# MasterCtrl.net
KiCad netlist of a schematic drawn in EasyEDA Pro
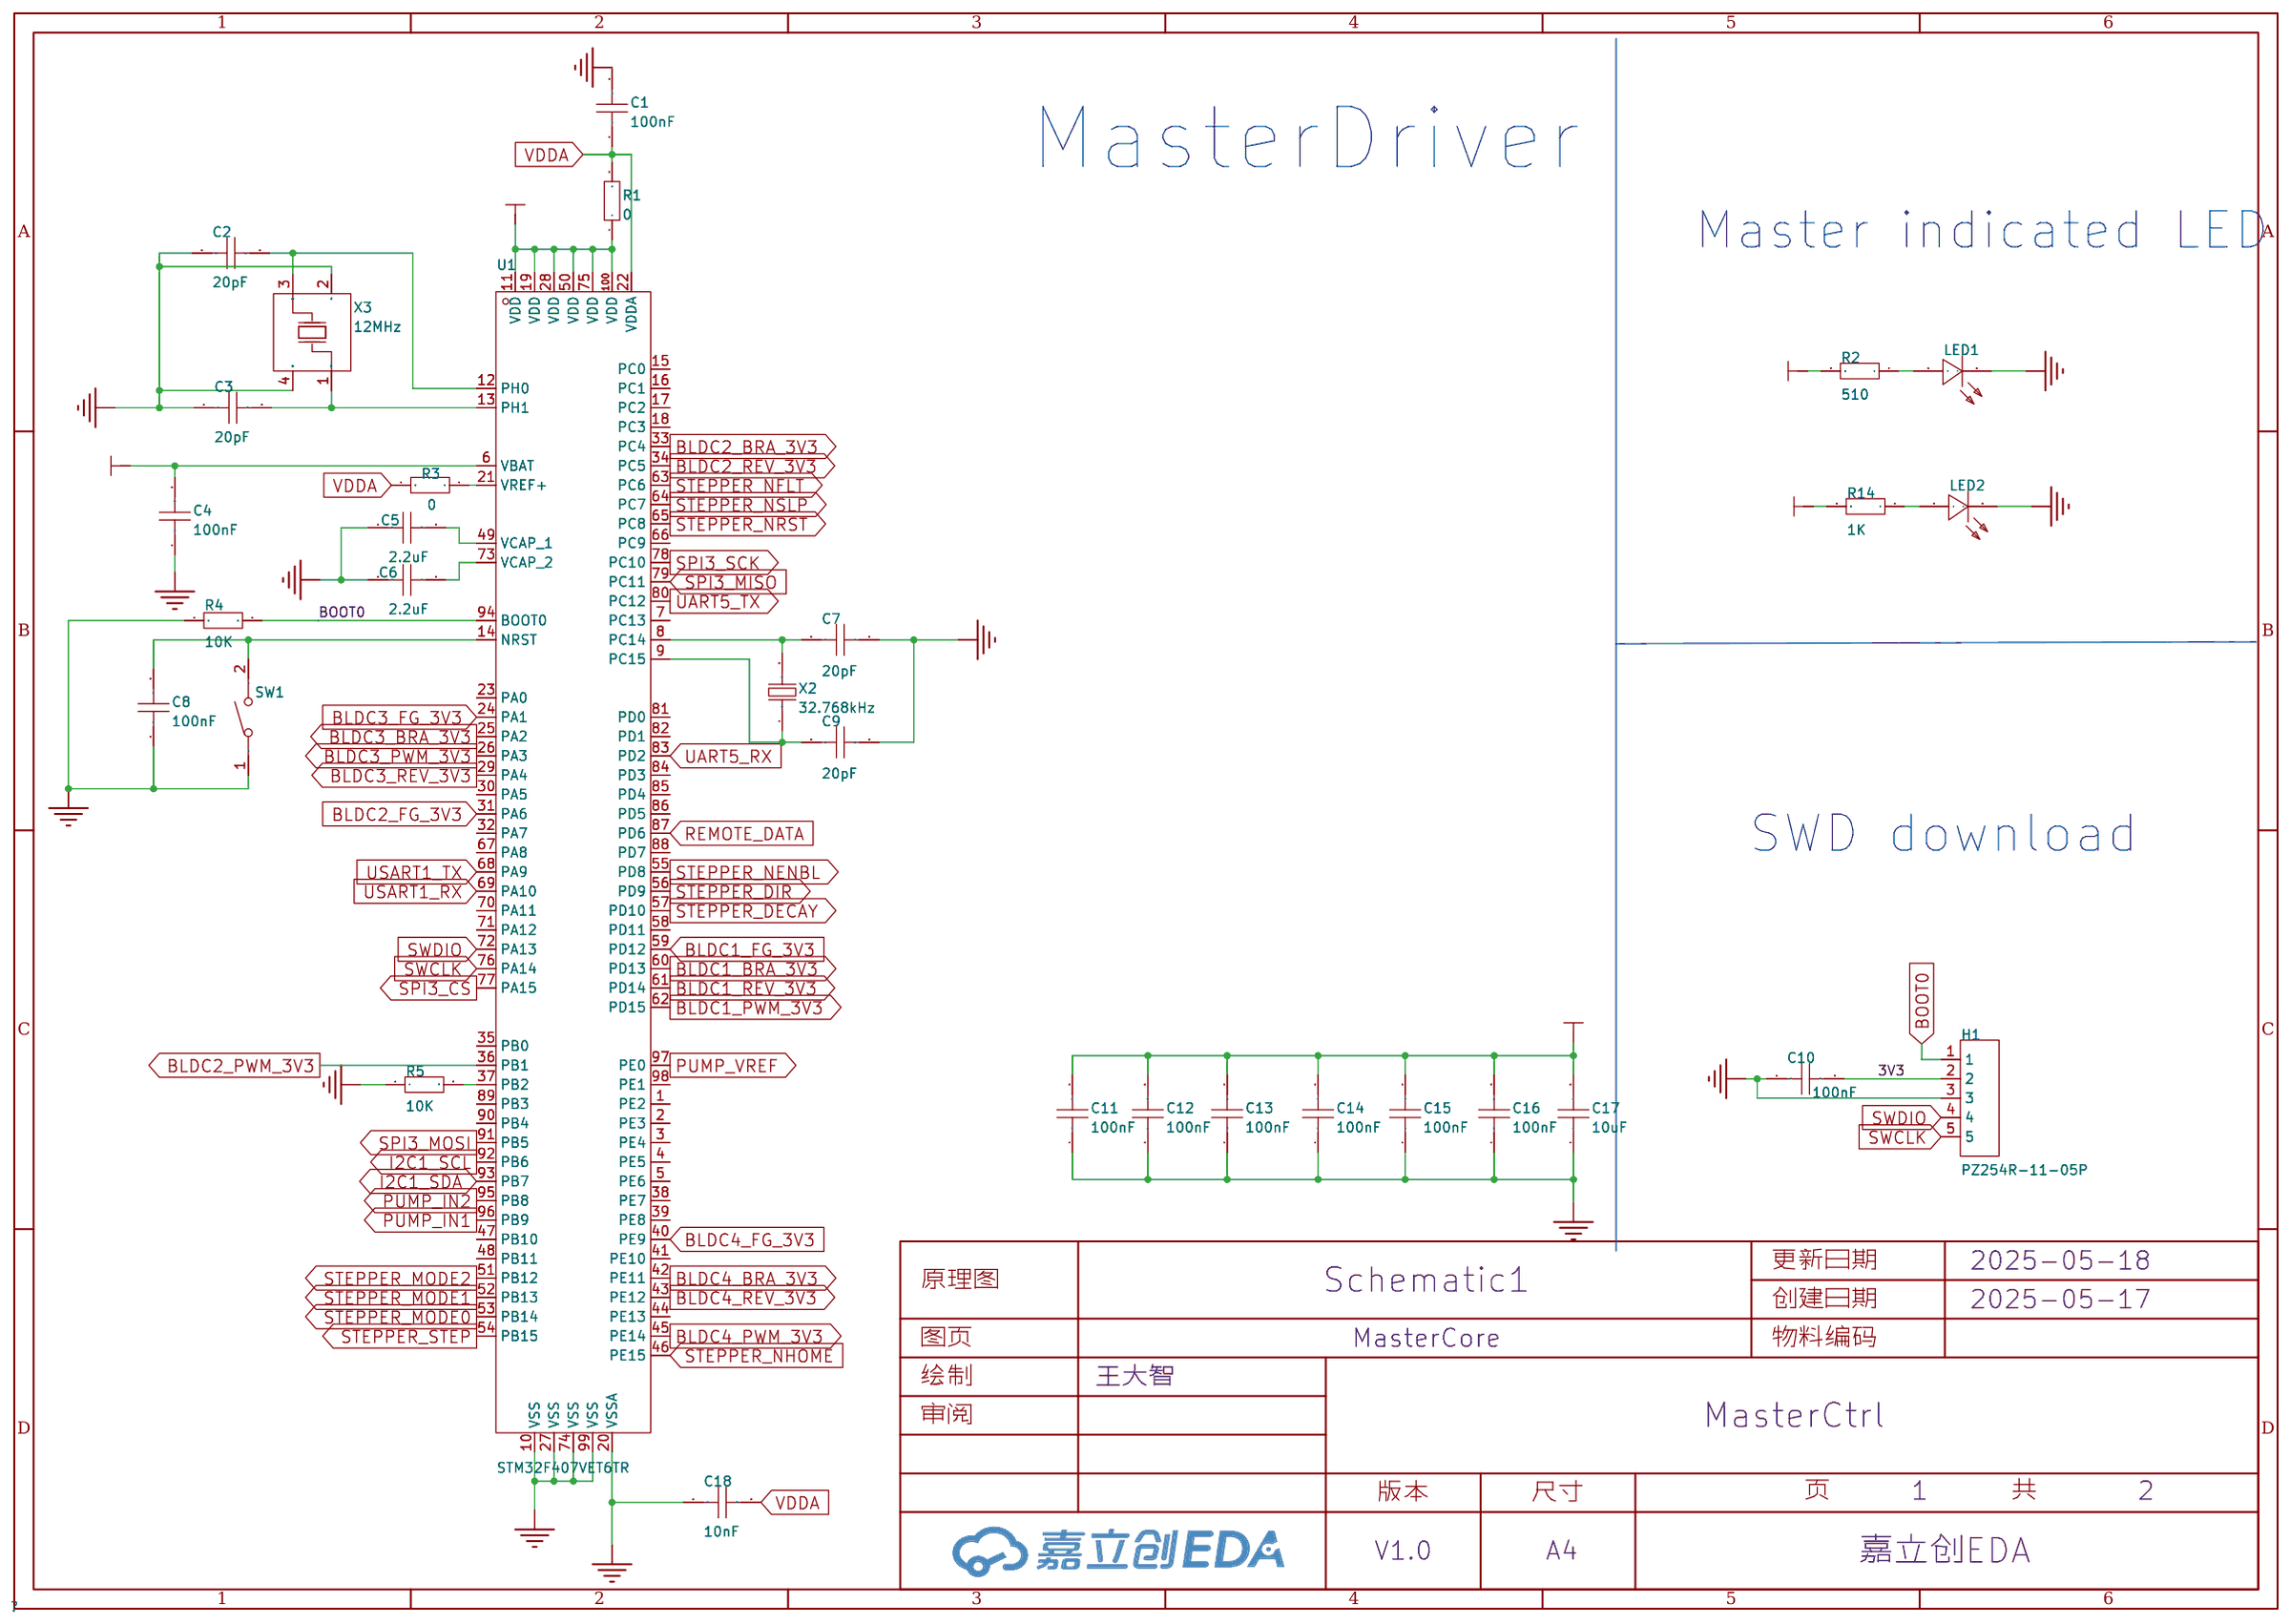
[diagram p0: MasterCore]
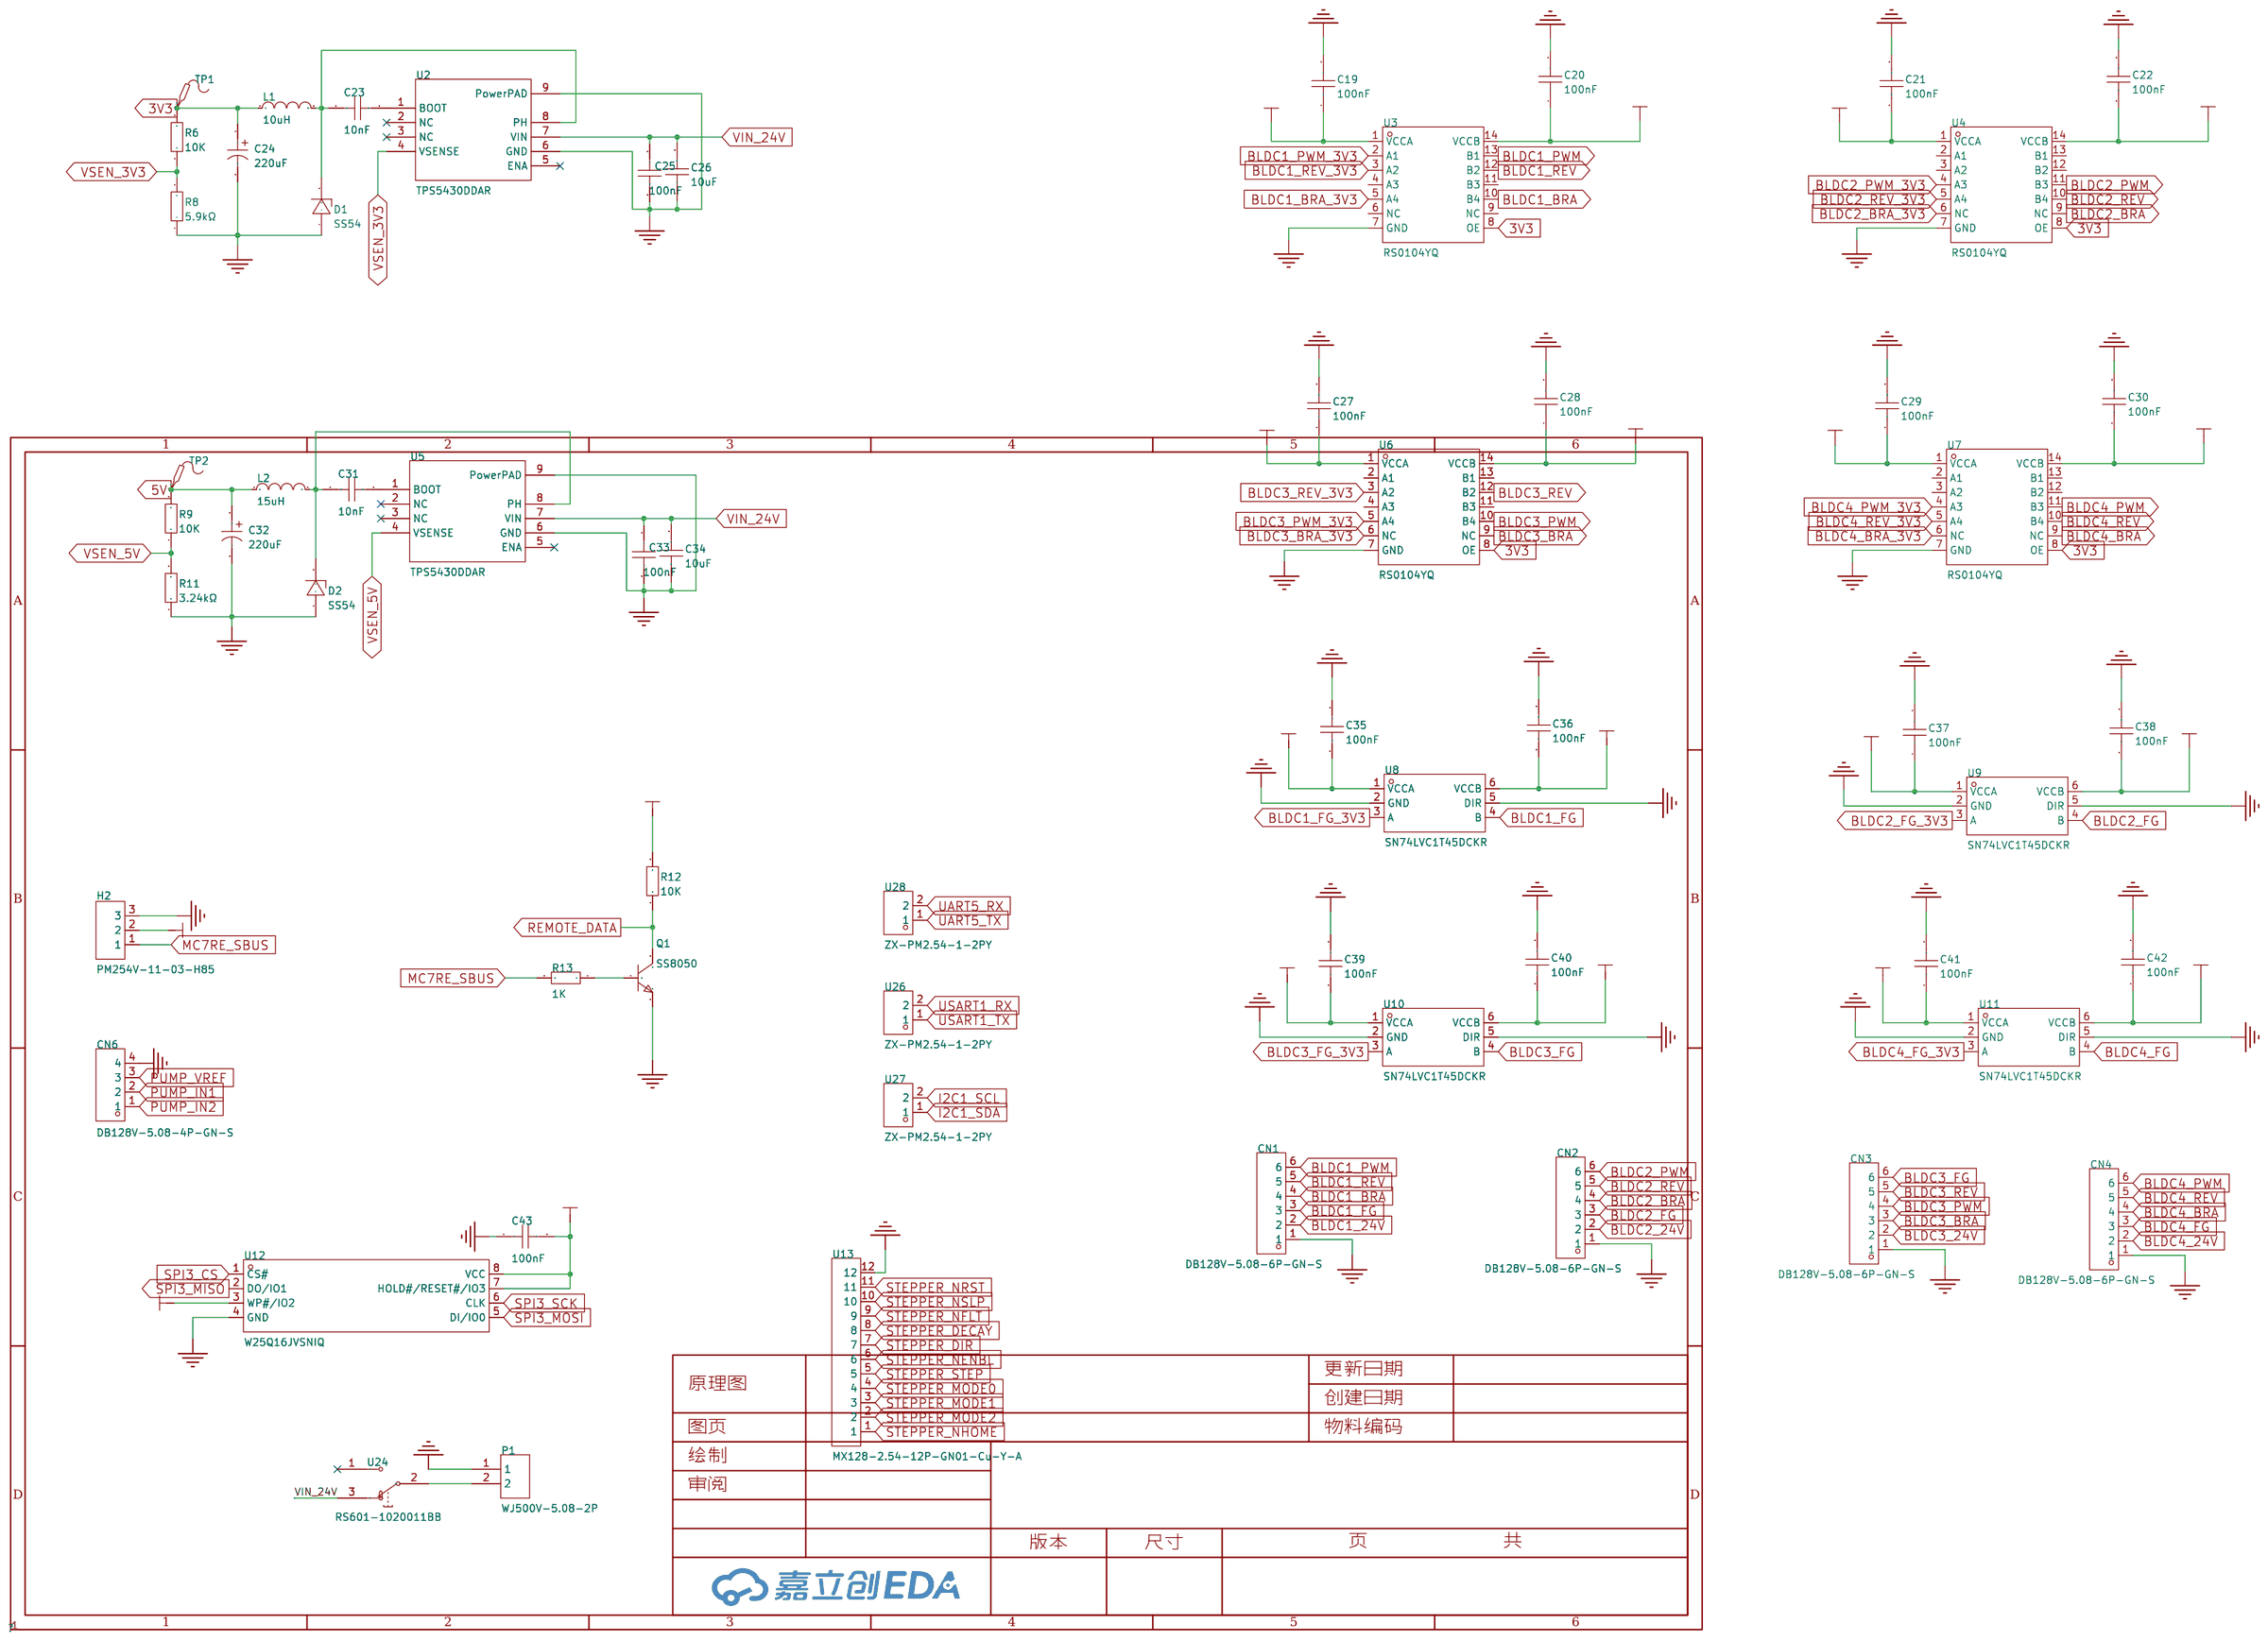
[diagram p1: ExternalCircuit]

(export (version "E")
  (design (tool "Eeschema 10.0.6"))
  (components
    (comp (ref "C1")
      (value "100nF")
      (footprint "easyedapro:C0603")
      (libsource (lib "easyedapro") (part "CapAcitance"))
    )
    (comp (ref "C2")
      (value "20pF")
      (footprint "easyedapro:C0603")
      (libsource (lib "easyedapro") (part "CapAcitance"))
    )
    (comp (ref "C3")
      (value "20pF")
      (footprint "easyedapro:C0603")
      (libsource (lib "easyedapro") (part "CapAcitance"))
    )
    (comp (ref "C4")
      (value "100nF")
      (footprint "easyedapro:C0603")
      (libsource (lib "easyedapro") (part "CapAcitance"))
    )
    (comp (ref "C5")
      (value "2.2uF")
      (footprint "easyedapro:C0603")
      (libsource (lib "easyedapro") (part "CapAcitance"))
    )
    (comp (ref "C6")
      (value "2.2uF")
      (footprint "easyedapro:C0603")
      (libsource (lib "easyedapro") (part "CapAcitance"))
    )
    (comp (ref "C7")
      (value "20pF")
      (footprint "easyedapro:C0603")
      (libsource (lib "easyedapro") (part "CapAcitance"))
    )
    (comp (ref "C8")
      (value "100nF")
      (footprint "easyedapro:C0603")
      (libsource (lib "easyedapro") (part "CapAcitance"))
    )
    (comp (ref "C9")
      (value "20pF")
      (footprint "easyedapro:C0603")
      (libsource (lib "easyedapro") (part "CapAcitance"))
    )
    (comp (ref "C10")
      (value "100nF")
      (footprint "easyedapro:C0603")
      (libsource (lib "easyedapro") (part "CapAcitance"))
    )
    (comp (ref "C11")
      (value "100nF")
      (footprint "easyedapro:C0603")
      (libsource (lib "easyedapro") (part "CapAcitance"))
    )
    (comp (ref "C12")
      (value "100nF")
      (footprint "easyedapro:C0603")
      (libsource (lib "easyedapro") (part "CapAcitance"))
    )
    (comp (ref "C13")
      (value "100nF")
      (footprint "easyedapro:C0603")
      (libsource (lib "easyedapro") (part "CapAcitance"))
    )
    (comp (ref "C14")
      (value "100nF")
      (footprint "easyedapro:C0603")
      (libsource (lib "easyedapro") (part "CapAcitance"))
    )
    (comp (ref "C15")
      (value "100nF")
      (footprint "easyedapro:C0603")
      (libsource (lib "easyedapro") (part "CapAcitance"))
    )
    (comp (ref "C16")
      (value "100nF")
      (footprint "easyedapro:C0603")
      (libsource (lib "easyedapro") (part "CapAcitance"))
    )
    (comp (ref "C17")
      (value "10uF")
      (footprint "easyedapro:C0603")
      (libsource (lib "easyedapro") (part "CapAcitance"))
    )
    (comp (ref "C18")
      (value "10nF")
      (footprint "easyedapro:C0603")
      (libsource (lib "easyedapro") (part "CapAcitance"))
    )
    (comp (ref "H1")
      (value "PZ254R-11-05P")
      (footprint "easyedapro:HDR-TH_5P-P2.54-H-M-W10.4")
      (fields (field (name "Manufacturer") "XFCN(兴飞)"))
      (libsource (lib "easyedapro") (part "PZ254R-11-05P"))
    )
    (comp (ref "LED1")
      (value "SZYY0805R")
      (footprint "easyedapro:LED0805-R-RD")
      (fields (field (name "Manufacturer") "yongyu(永裕光电)"))
      (libsource (lib "easyedapro") (part "SZYY0805R"))
    )
    (comp (ref "LED2")
      (value "SZYY0805R")
      (footprint "easyedapro:LED0805-R-RD")
      (fields (field (name "Manufacturer") "yongyu(永裕光电)"))
      (libsource (lib "easyedapro") (part "SZYY0805R"))
    )
    (comp (ref "R1") (value "0") (footprint "easyedapro:R0603") (libsource (lib "easyedapro") (part "电阻")))
    (comp (ref "R2") (value "510") (footprint "easyedapro:R0603") (libsource (lib "easyedapro") (part "电阻")))
    (comp (ref "R3") (value "0") (footprint "easyedapro:R0603") (libsource (lib "easyedapro") (part "电阻")))
    (comp (ref "R4") (value "10K") (footprint "easyedapro:R0603") (libsource (lib "easyedapro") (part "电阻")))
    (comp (ref "R5") (value "10K") (footprint "easyedapro:R0603") (libsource (lib "easyedapro") (part "电阻")))
    (comp (ref "R14") (value "1K") (footprint "easyedapro:R0603") (libsource (lib "easyedapro") (part "电阻")))
    (comp (ref "SW1")
      (value "TS-1088-AR02016")
      (footprint "easyedapro:SW-SMD_L3.9-W3.0-P4.45")
      (fields (field (name "Manufacturer") "XUNPU(讯普)"))
      (libsource (lib "easyedapro") (part "TS-1088-AR02016"))
    )
    (comp (ref "U1")
      (value "STM32F407VET6TR")
      (footprint "easyedapro:LQFP-100_L14.0-W14.0-P0.50-LS16.0-BL")
      (description "CPU内核:ARM-M4;CPU最大主频:168MHz;应用领域:-;")
      (fields (field (name "Manufacturer") "ST(意法半导体)"))
      (libsource (lib "easyedapro") (part "STM32F407VET6TR"))
    )
    (comp (ref "X2")
      (value "32.768kHz")
      (footprint "easyedapro:FC-135R_L3.2-W1.5")
      (description "晶振类型:贴片晶振;频率:32.768kHz;常温频差:±20ppm;负载电容:12.5pF;")
      (fields (field (name "Manufacturer Part") "Q13FC13500004") (field (name "Manufacturer") "EPSON(爱普生)"))
      (libsource (lib "easyedapro") (part "Q13FC1350000400"))
    )
    (comp (ref "X3")
      (value "12MHz")
      (footprint "easyedapro:CRYSTAL-SMD_4P-L3.2-W2.5-BL")
      (description "晶振类型:贴片晶振;频率:12MHz;常温频差:±10ppm;负载电容:20pF;频率稳定度:±20ppm;")
      (fields (field (name "Manufacturer Part") "X322512MSB4SI") (field (name "Manufacturer") "YXC(扬兴晶振)"))
      (libsource (lib "easyedapro") (part "X322512MSB4SI"))
    )
    (comp (ref "C19")
      (value "100nF")
      (footprint "easyedapro:C0603")
      (libsource (lib "easyedapro") (part "CapAcitance"))
    )
    (comp (ref "C20")
      (value "100nF")
      (footprint "easyedapro:C0603")
      (libsource (lib "easyedapro") (part "CapAcitance"))
    )
    (comp (ref "C21")
      (value "100nF")
      (footprint "easyedapro:C0603")
      (libsource (lib "easyedapro") (part "CapAcitance"))
    )
    (comp (ref "C22")
      (value "100nF")
      (footprint "easyedapro:C0603")
      (libsource (lib "easyedapro") (part "CapAcitance"))
    )
    (comp (ref "C23")
      (value "10nF")
      (footprint "easyedapro:C0603")
      (libsource (lib "easyedapro") (part "CapAcitance"))
    )
    (comp (ref "C24")
      (value "220uF")
      (footprint "easyedapro:CAP-SMD_BD8.0-L8.3-W8.3-FD")
      (description "容值:220uF;精度:±20%;额定电压:35V;纹波电流:175mA@120Hz;")
      (fields
        (field (name "Manufacturer Part") "GVT1V227M0810CNVC")
        (field (name "Manufacturer") "HRK(鸿瑞凯电子)")
      )
      (libsource (lib "easyedapro") (part "GVT1V227M0810CNVC"))
    )
    (comp (ref "C25")
      (value "100nF")
      (footprint "easyedapro:C0603")
      (libsource (lib "easyedapro") (part "CapAcitance"))
    )
    (comp (ref "C26")
      (value "10uF")
      (footprint "easyedapro:C1206")
      (description "容值:10uF;精度:±10%;额定电压:50V;温度系数:X5R;")
      (fields
        (field (name "Manufacturer Part") "HGC1206R5106K500NSPJ")
        (field (name "Manufacturer") "Chinocera(华瓷)")
      )
      (libsource (lib "easyedapro") (part "HGC1206R5106K500NSPJ"))
    )
    (comp (ref "C27")
      (value "100nF")
      (footprint "easyedapro:C0603")
      (libsource (lib "easyedapro") (part "CapAcitance"))
    )
    (comp (ref "C28")
      (value "100nF")
      (footprint "easyedapro:C0603")
      (libsource (lib "easyedapro") (part "CapAcitance"))
    )
    (comp (ref "C29")
      (value "100nF")
      (footprint "easyedapro:C0603")
      (libsource (lib "easyedapro") (part "CapAcitance"))
    )
    (comp (ref "C30")
      (value "100nF")
      (footprint "easyedapro:C0603")
      (libsource (lib "easyedapro") (part "CapAcitance"))
    )
    (comp (ref "C31")
      (value "10nF")
      (footprint "easyedapro:C0603")
      (libsource (lib "easyedapro") (part "CapAcitance"))
    )
    (comp (ref "C32")
      (value "220uF")
      (footprint "easyedapro:CAP-SMD_BD8.0-L8.3-W8.3-FD")
      (description "容值:220uF;精度:±20%;额定电压:35V;纹波电流:175mA@120Hz;")
      (fields
        (field (name "Manufacturer Part") "GVT1V227M0810CNVC")
        (field (name "Manufacturer") "HRK(鸿瑞凯电子)")
      )
      (libsource (lib "easyedapro") (part "GVT1V227M0810CNVC"))
    )
    (comp (ref "C33")
      (value "100nF")
      (footprint "easyedapro:C0603")
      (libsource (lib "easyedapro") (part "CapAcitance"))
    )
    (comp (ref "C34")
      (value "10uF")
      (footprint "easyedapro:C1206")
      (description "容值:10uF;精度:±10%;额定电压:50V;温度系数:X5R;")
      (fields
        (field (name "Manufacturer Part") "HGC1206R5106K500NSPJ")
        (field (name "Manufacturer") "Chinocera(华瓷)")
      )
      (libsource (lib "easyedapro") (part "HGC1206R5106K500NSPJ"))
    )
    (comp (ref "C35")
      (value "100nF")
      (footprint "easyedapro:C0603")
      (libsource (lib "easyedapro") (part "CapAcitance"))
    )
    (comp (ref "C36")
      (value "100nF")
      (footprint "easyedapro:C0603")
      (libsource (lib "easyedapro") (part "CapAcitance"))
    )
    (comp (ref "C37")
      (value "100nF")
      (footprint "easyedapro:C0603")
      (libsource (lib "easyedapro") (part "CapAcitance"))
    )
    (comp (ref "C38")
      (value "100nF")
      (footprint "easyedapro:C0603")
      (libsource (lib "easyedapro") (part "CapAcitance"))
    )
    (comp (ref "C39")
      (value "100nF")
      (footprint "easyedapro:C0603")
      (libsource (lib "easyedapro") (part "CapAcitance"))
    )
    (comp (ref "C40")
      (value "100nF")
      (footprint "easyedapro:C0603")
      (libsource (lib "easyedapro") (part "CapAcitance"))
    )
    (comp (ref "C41")
      (value "100nF")
      (footprint "easyedapro:C0603")
      (libsource (lib "easyedapro") (part "CapAcitance"))
    )
    (comp (ref "C42")
      (value "100nF")
      (footprint "easyedapro:C0603")
      (libsource (lib "easyedapro") (part "CapAcitance"))
    )
    (comp (ref "C43")
      (value "100nF")
      (footprint "easyedapro:C0603")
      (libsource (lib "easyedapro") (part "CapAcitance"))
    )
    (comp (ref "CN1")
      (value "DB128V-5.08-6P-GN-S")
      (footprint "easyedapro:CONN-TH_6P-P5.08_DIBO_DB128V-5.08")
      (fields (field (name "Manufacturer") "DORABO(地博电气)"))
      (libsource (lib "easyedapro") (part "DB128V-5.08-6P-GN-S"))
    )
    (comp (ref "CN2")
      (value "DB128V-5.08-6P-GN-S")
      (footprint "easyedapro:CONN-TH_6P-P5.08_DIBO_DB128V-5.08")
      (fields (field (name "Manufacturer") "DORABO(地博电气)"))
      (libsource (lib "easyedapro") (part "DB128V-5.08-6P-GN-S"))
    )
    (comp (ref "CN3")
      (value "DB128V-5.08-6P-GN-S")
      (footprint "easyedapro:CONN-TH_6P-P5.08_DIBO_DB128V-5.08")
      (fields (field (name "Manufacturer") "DORABO(地博电气)"))
      (libsource (lib "easyedapro") (part "DB128V-5.08-6P-GN-S"))
    )
    (comp (ref "CN4")
      (value "DB128V-5.08-6P-GN-S")
      (footprint "easyedapro:CONN-TH_6P-P5.08_DIBO_DB128V-5.08")
      (fields (field (name "Manufacturer") "DORABO(地博电气)"))
      (libsource (lib "easyedapro") (part "DB128V-5.08-6P-GN-S"))
    )
    (comp (ref "CN6")
      (value "DB128V-5.08-4P-GN-S")
      (footprint "easyedapro:CONN-TH_4P-P5.08_DIBO_DB128V-5.08")
      (fields (field (name "Manufacturer") "DORABO(地博电气)"))
      (libsource (lib "easyedapro") (part "DB128V-5.08-4P-GN-S"))
    )
    (comp (ref "D1")
      (value "SS54")
      (footprint "easyedapro:SMA_L4.3-W2.6-LS5.0-FD")
      (description "二极管配置:独立式;正向压降(Vf):550mV@5.0A;直流反向耐压(Vr):40V;整流电流:5A;")
      (fields (field (name "Manufacturer") "宏迦橙"))
      (libsource (lib "easyedapro") (part "SS54_C7420369"))
    )
    (comp (ref "D2")
      (value "SS54")
      (footprint "easyedapro:SMA_L4.3-W2.6-LS5.0-FD")
      (description "二极管配置:独立式;正向压降(Vf):550mV@5.0A;直流反向耐压(Vr):40V;整流电流:5A;")
      (fields (field (name "Manufacturer") "宏迦橙"))
      (libsource (lib "easyedapro") (part "SS54_C7420369"))
    )
    (comp (ref "H2")
      (value "PM254V-11-03-H85")
      (footprint "easyedapro:HDR-TH_3P-P2.54-V-F")
      (description "插孔结构:1x3P;间距:2.54mm;行距:-;安装类型:直插;排数:单排;总孔位数:3P;塑高:-;触头材质:黄铜;触头镀层:-;")
      (fields (field (name "Manufacturer") "XFCN(兴飞)"))
      (libsource (lib "easyedapro") (part "PM254V-11-03-H85"))
    )
    (comp (ref "L1")
      (value "10uH")
      (footprint "easyedapro:IND-SMD_L7.3-W6.8")
      (description "电感值:10uH;精度:±20%;额定电流:4.5A;饱和电流(Isat):5.5A;类型:一体成型电感;")
      (fields (field (name "Manufacturer Part") "FXL0630-100-M") (field (name "Manufacturer") "cjiang(长江微电)"))
      (libsource (lib "easyedapro") (part "FXL0630-100-M"))
    )
    (comp (ref "L2")
      (value "15uH")
      (footprint "easyedapro:IND-SMD_L7.0-W6.6_FXL0630")
      (description "电感值:15uH;精度:±20%;额定电流:3A;饱和电流(Isat):4.5A;类型:一体成型电感;")
      (fields (field (name "Manufacturer Part") "FXL0630-150-M") (field (name "Manufacturer") "cjiang(长江微电)"))
      (libsource (lib "easyedapro") (part "FXL0630-150-M"))
    )
    (comp (ref "P1")
      (value "WJ500V-5.08-2P")
      (footprint "easyedapro:CONN-TH_2P-P5.00_WJ500V-5.08-2P")
      (fields (field (name "Manufacturer") "KANGNEX(康奈克斯电气)"))
      (libsource (lib "easyedapro") (part "WJ500V-5.08-2P-14-00A"))
    )
    (comp (ref "Q1")
      (value "SS8050")
      (footprint "easyedapro:SOT-23-3_L2.9-W1.3-P1.90-LS2.4-BR")
      (description "晶体管类型:NPN;集电极电流(Ic):1.5A;集射极击穿电压(Vceo):25V;耗散功率(Pd):300mW;直流电流增益(hFE):120@100mA,1.0V;")
      (fields (field (name "Manufacturer") "宏嘉诚"))
      (libsource (lib "easyedapro") (part "SS8050_C7420370"))
    )
    (comp (ref "R6") (value "10K") (footprint "easyedapro:R0603") (libsource (lib "easyedapro") (part "电阻")))
    (comp (ref "R8")
      (value "5.9kΩ")
      (footprint "easyedapro:R0603")
      (description "电阻类型:厚膜电阻;阻值:5.9kΩ;精度:±1%;功率:100mW;最大工作电压:75V;温度系数:±100ppm/°C;")
      (fields
        (field (name "Manufacturer Part") "0603WAF5901T5E")
        (field (name "Manufacturer") "UNI-ROYAL(厚声)")
      )
      (libsource (lib "easyedapro") (part "0603WAF5901T5E"))
    )
    (comp (ref "R9") (value "10K") (footprint "easyedapro:R0603") (libsource (lib "easyedapro") (part "电阻")))
    (comp (ref "R11")
      (value "3.24kΩ")
      (footprint "easyedapro:R0603")
      (description "电阻类型:厚膜电阻;阻值:3.24kΩ;精度:±1%;功率:100mW;最大工作电压:75V;温度系数:±100ppm/°C;")
      (fields
        (field (name "Manufacturer Part") "0603WAF3241T5E")
        (field (name "Manufacturer") "UNI-ROYAL(厚声)")
      )
      (libsource (lib "easyedapro") (part "0603WAF3241T5E"))
    )
    (comp (ref "R12") (value "10K") (footprint "easyedapro:R0603") (libsource (lib "easyedapro") (part "电阻")))
    (comp (ref "R13") (value "1K") (footprint "easyedapro:R0603") (libsource (lib "easyedapro") (part "电阻")))
    (comp (ref "TP1")
      (value "~")
      (footprint "easyedapro:Test-Point-0.5mm")
      (description "Test Point 测试点")
      (libsource (lib "easyedapro") (part "Test-Point"))
    )
    (comp (ref "TP2")
      (value "~")
      (footprint "easyedapro:Test-Point-0.5mm")
      (description "Test Point 测试点")
      (libsource (lib "easyedapro") (part "Test-Point"))
    )
    (comp (ref "U2")
      (value "TPS5430DDAR")
      (footprint "easyedapro:ESOP-8_L4.9-W3.9-P1.27-LS6.0-TL-EP")
      (description "功能类型:降压型;输出类型:可调;工作电压:5.5V~36V;输出电压:1.221V~32.04V;输出电流:3A;")
      (fields (field (name "Manufacturer") "TI(德州仪器)"))
      (libsource (lib "easyedapro") (part "TPS5430DDAR"))
    )
    (comp (ref "U3")
      (value "RS0104YQ")
      (footprint "easyedapro:TSSOP-14_L5.0-W4.4-P0.65-LS6.4-BL")
      (description "数据速率:24Mbps;电压(VCCA):1.65V~5.5V;电压(VCCB):2.3V~5.5V;电路数:1;每个电路通道数:4;")
      (fields (field (name "Manufacturer") "RUNIC(润石)"))
      (libsource (lib "easyedapro") (part "RS0104YQ"))
    )
    (comp (ref "U4")
      (value "RS0104YQ")
      (footprint "easyedapro:TSSOP-14_L5.0-W4.4-P0.65-LS6.4-BL")
      (description "数据速率:24Mbps;电压(VCCA):1.65V~5.5V;电压(VCCB):2.3V~5.5V;电路数:1;每个电路通道数:4;")
      (fields (field (name "Manufacturer") "RUNIC(润石)"))
      (libsource (lib "easyedapro") (part "RS0104YQ"))
    )
    (comp (ref "U5")
      (value "TPS5430DDAR")
      (footprint "easyedapro:ESOP-8_L4.9-W3.9-P1.27-LS6.0-TL-EP")
      (description "功能类型:降压型;输出类型:可调;工作电压:5.5V~36V;输出电压:1.221V~32.04V;输出电流:3A;")
      (fields (field (name "Manufacturer") "TI(德州仪器)"))
      (libsource (lib "easyedapro") (part "TPS5430DDAR"))
    )
    (comp (ref "U6")
      (value "RS0104YQ")
      (footprint "easyedapro:TSSOP-14_L5.0-W4.4-P0.65-LS6.4-BL")
      (description "数据速率:24Mbps;电压(VCCA):1.65V~5.5V;电压(VCCB):2.3V~5.5V;电路数:1;每个电路通道数:4;")
      (fields (field (name "Manufacturer") "RUNIC(润石)"))
      (libsource (lib "easyedapro") (part "RS0104YQ"))
    )
    (comp (ref "U7")
      (value "RS0104YQ")
      (footprint "easyedapro:TSSOP-14_L5.0-W4.4-P0.65-LS6.4-BL")
      (description "数据速率:24Mbps;电压(VCCA):1.65V~5.5V;电压(VCCB):2.3V~5.5V;电路数:1;每个电路通道数:4;")
      (fields (field (name "Manufacturer") "RUNIC(润石)"))
      (libsource (lib "easyedapro") (part "RS0104YQ"))
    )
    (comp (ref "U8")
      (value "SN74LVC1T45DCKR")
      (footprint "easyedapro:SC-70-6_L2.2-W1.3-P0.65-LS2.2-BR")
      (description "数据速率:420Mbps;电压(VCCA):1.65V~5.5V;电压(VCCB):1.65V~5.5V;电路数:1;每个电路通道数:1;")
      (fields (field (name "Manufacturer") "TI(德州仪器)"))
      (libsource (lib "easyedapro") (part "SN74LVC1T45DCKR"))
    )
    (comp (ref "U9")
      (value "SN74LVC1T45DCKR")
      (footprint "easyedapro:SC-70-6_L2.2-W1.3-P0.65-LS2.2-BR")
      (description "数据速率:420Mbps;电压(VCCA):1.65V~5.5V;电压(VCCB):1.65V~5.5V;电路数:1;每个电路通道数:1;")
      (fields (field (name "Manufacturer") "TI(德州仪器)"))
      (libsource (lib "easyedapro") (part "SN74LVC1T45DCKR"))
    )
    (comp (ref "U10")
      (value "SN74LVC1T45DCKR")
      (footprint "easyedapro:SC-70-6_L2.2-W1.3-P0.65-LS2.2-BR")
      (description "数据速率:420Mbps;电压(VCCA):1.65V~5.5V;电压(VCCB):1.65V~5.5V;电路数:1;每个电路通道数:1;")
      (fields (field (name "Manufacturer") "TI(德州仪器)"))
      (libsource (lib "easyedapro") (part "SN74LVC1T45DCKR"))
    )
    (comp (ref "U11")
      (value "SN74LVC1T45DCKR")
      (footprint "easyedapro:SC-70-6_L2.2-W1.3-P0.65-LS2.2-BR")
      (description "数据速率:420Mbps;电压(VCCA):1.65V~5.5V;电压(VCCB):1.65V~5.5V;电路数:1;每个电路通道数:1;")
      (fields (field (name "Manufacturer") "TI(德州仪器)"))
      (libsource (lib "easyedapro") (part "SN74LVC1T45DCKR"))
    )
    (comp (ref "U12")
      (value "W25Q16JVSNIQ")
      (footprint "easyedapro:SOP-8_L4.9-W3.9-P1.27-LS6.0-BL")
      (fields (field (name "Manufacturer") "WINBOND(华邦)"))
      (libsource (lib "easyedapro") (part "W25Q16JVSNIQ TR"))
    )
    (comp (ref "U13")
      (value "MX128-2.54-12P-GN01-Cu-Y-A")
      (footprint "easyedapro:CONN-TH_12P-P2.54_MX128-2.54-12P-GN01-CU-Y-A")
      (fields (field (name "Manufacturer") "MAX(迈旭)"))
      (libsource (lib "easyedapro") (part "MX128-2.54-12P-GN01-CU-Y-A"))
    )
    (comp (ref "U24")
      (value "RS601-1020011BB")
      (footprint "easyedapro:SW-TH_RS601-1020011BB")
      (description "带灯:无;引脚样式:焊片;额定电流:8A;额定电压(AC):250V;额定电压(DC):-;电路结构:单刀双掷;机械寿命:1万次;")
      (fields (field (name "Manufacturer") "HCTL(华灿天禄)"))
      (libsource (lib "easyedapro") (part "RS601-1020011BB"))
    )
    (comp (ref "U26")
      (value "ZX-PM2.54-1-2PY")
      (footprint "easyedapro:HDR-TH_2P-P2.54-V-F")
      (fields (field (name "Manufacturer") "Megastar(兆星)"))
      (libsource (lib "easyedapro") (part "ZX-PM2.54-1-2PY"))
    )
    (comp (ref "U27")
      (value "ZX-PM2.54-1-2PY")
      (footprint "easyedapro:HDR-TH_2P-P2.54-V-F")
      (fields (field (name "Manufacturer") "Megastar(兆星)"))
      (libsource (lib "easyedapro") (part "ZX-PM2.54-1-2PY"))
    )
    (comp (ref "U28")
      (value "ZX-PM2.54-1-2PY")
      (footprint "easyedapro:HDR-TH_2P-P2.54-V-F")
      (fields (field (name "Manufacturer") "Megastar(兆星)"))
      (libsource (lib "easyedapro") (part "ZX-PM2.54-1-2PY"))
    )
  )
  (nets
    (net (code "1") (name "3V3") (class "Default")
      (node (ref "C10") (pin "2") (pinfunction "2_2") (pintype "input"))
      (node (ref "C11") (pin "2") (pinfunction "2_2") (pintype "input"))
      (node (ref "C12") (pin "2") (pinfunction "2_2") (pintype "input"))
      (node (ref "C13") (pin "2") (pinfunction "2_2") (pintype "input"))
      (node (ref "C14") (pin "2") (pinfunction "2_2") (pintype "input"))
      (node (ref "C15") (pin "2") (pinfunction "2_2") (pintype "input"))
      (node (ref "C16") (pin "2") (pinfunction "2_2") (pintype "input"))
      (node (ref "C17") (pin "2") (pinfunction "2_2") (pintype "input"))
      (node (ref "C19") (pin "1") (pinfunction "1_1") (pintype "input"))
      (node (ref "C21") (pin "1") (pinfunction "1_1") (pintype "input"))
      (node (ref "C24") (pin "1") (pinfunction "1_1") (pintype "input"))
      (node (ref "C27") (pin "1") (pinfunction "1_1") (pintype "input"))
      (node (ref "C29") (pin "1") (pinfunction "1_1") (pintype "input"))
      (node (ref "C35") (pin "1") (pinfunction "1_1") (pintype "input"))
      (node (ref "C37") (pin "1") (pinfunction "1_1") (pintype "input"))
      (node (ref "C39") (pin "1") (pinfunction "1_1") (pintype "input"))
      (node (ref "C4") (pin "2") (pinfunction "2_2") (pintype "input"))
      (node (ref "C41") (pin "1") (pinfunction "1_1") (pintype "input"))
      (node (ref "C43") (pin "2") (pinfunction "2_2") (pintype "input"))
      (node (ref "H1") (pin "2") (pinfunction "2_2") (pintype "unspecified"))
      (node (ref "L1") (pin "1") (pinfunction "1_1") (pintype "unspecified"))
      (node (ref "R1") (pin "1") (pinfunction "1_1") (pintype "input"))
      (node (ref "R12") (pin "2") (pinfunction "2_2") (pintype "input"))
      (node (ref "R2") (pin "2") (pinfunction "2_2") (pintype "input"))
      (node (ref "R6") (pin "2") (pinfunction "2_2") (pintype "input"))
      (node (ref "TP1") (pin "1") (pinfunction "1_1") (pintype "input"))
      (node (ref "U1") (pin "100") (pinfunction "VDD_100") (pintype "unspecified"))
      (node (ref "U1") (pin "11") (pinfunction "VDD_11") (pintype "unspecified"))
      (node (ref "U1") (pin "19") (pinfunction "VDD_19") (pintype "unspecified"))
      (node (ref "U1") (pin "28") (pinfunction "VDD_28") (pintype "unspecified"))
      (node (ref "U1") (pin "50") (pinfunction "VDD_50") (pintype "unspecified"))
      (node (ref "U1") (pin "6") (pinfunction "VBAT_6") (pintype "unspecified"))
      (node (ref "U1") (pin "75") (pinfunction "VDD_75") (pintype "unspecified"))
      (node (ref "U10") (pin "1") (pinfunction "VCCA_1") (pintype "unspecified"))
      (node (ref "U11") (pin "1") (pinfunction "VCCA_1") (pintype "unspecified"))
      (node (ref "U12") (pin "3") (pinfunction "WP#/IO2_3") (pintype "unspecified"))
      (node (ref "U12") (pin "7") (pinfunction "HOLD#/RESET#/IO3_7") (pintype "unspecified"))
      (node (ref "U12") (pin "8") (pinfunction "VCC_8") (pintype "unspecified"))
      (node (ref "U3") (pin "1") (pinfunction "VCCA_1") (pintype "unspecified"))
      (node (ref "U3") (pin "8") (pinfunction "OE_8") (pintype "unspecified"))
      (node (ref "U4") (pin "1") (pinfunction "VCCA_1") (pintype "unspecified"))
      (node (ref "U4") (pin "8") (pinfunction "OE_8") (pintype "unspecified"))
      (node (ref "U6") (pin "1") (pinfunction "VCCA_1") (pintype "unspecified"))
      (node (ref "U6") (pin "8") (pinfunction "OE_8") (pintype "unspecified"))
      (node (ref "U7") (pin "1") (pinfunction "VCCA_1") (pintype "unspecified"))
      (node (ref "U7") (pin "8") (pinfunction "OE_8") (pintype "unspecified"))
      (node (ref "U8") (pin "1") (pinfunction "VCCA_1") (pintype "unspecified"))
      (node (ref "U9") (pin "1") (pinfunction "VCCA_1") (pintype "unspecified"))
    )
    (net (code "2") (name "5V") (class "Default")
      (node (ref "C20") (pin "1") (pinfunction "1_1") (pintype "input"))
      (node (ref "C22") (pin "1") (pinfunction "1_1") (pintype "input"))
      (node (ref "C28") (pin "1") (pinfunction "1_1") (pintype "input"))
      (node (ref "C30") (pin "1") (pinfunction "1_1") (pintype "input"))
      (node (ref "C32") (pin "1") (pinfunction "1_1") (pintype "input"))
      (node (ref "C36") (pin "1") (pinfunction "1_1") (pintype "input"))
      (node (ref "C38") (pin "1") (pinfunction "1_1") (pintype "input"))
      (node (ref "C40") (pin "1") (pinfunction "1_1") (pintype "input"))
      (node (ref "C42") (pin "1") (pinfunction "1_1") (pintype "input"))
      (node (ref "H2") (pin "2") (pinfunction "2_2") (pintype "unspecified"))
      (node (ref "L2") (pin "1") (pinfunction "1_1") (pintype "unspecified"))
      (node (ref "R14") (pin "2") (pinfunction "2_2") (pintype "input"))
      (node (ref "R9") (pin "2") (pinfunction "2_2") (pintype "input"))
      (node (ref "TP2") (pin "1") (pinfunction "1_1") (pintype "input"))
      (node (ref "U10") (pin "6") (pinfunction "VCCB_6") (pintype "unspecified"))
      (node (ref "U11") (pin "6") (pinfunction "VCCB_6") (pintype "unspecified"))
      (node (ref "U3") (pin "14") (pinfunction "VCCB_14") (pintype "unspecified"))
      (node (ref "U4") (pin "14") (pinfunction "VCCB_14") (pintype "unspecified"))
      (node (ref "U6") (pin "14") (pinfunction "VCCB_14") (pintype "unspecified"))
      (node (ref "U7") (pin "14") (pinfunction "VCCB_14") (pintype "unspecified"))
      (node (ref "U8") (pin "6") (pinfunction "VCCB_6") (pintype "unspecified"))
      (node (ref "U9") (pin "6") (pinfunction "VCCB_6") (pintype "unspecified"))
    )
    (net (code "3") (name "BLDC1_24V") (class "Default")
      (node (ref "CN1") (pin "2") (pinfunction "2_2") (pintype "unspecified"))
    )
    (net (code "4") (name "BLDC1_BRA") (class "Default")
      (node (ref "CN1") (pin "4") (pinfunction "4_4") (pintype "unspecified"))
      (node (ref "U3") (pin "10") (pinfunction "B4_10") (pintype "unspecified"))
    )
    (net (code "5") (name "BLDC1_BRA_3V3") (class "Default")
      (node (ref "U1") (pin "60") (pinfunction "PD13_60") (pintype "unspecified"))
      (node (ref "U3") (pin "5") (pinfunction "A4_5") (pintype "unspecified"))
    )
    (net (code "6") (name "BLDC1_FG") (class "Default")
      (node (ref "CN1") (pin "3") (pinfunction "3_3") (pintype "unspecified"))
      (node (ref "U8") (pin "4") (pinfunction "B_4") (pintype "unspecified"))
    )
    (net (code "7") (name "BLDC1_FG_3V3") (class "Default")
      (node (ref "U1") (pin "59") (pinfunction "PD12_59") (pintype "unspecified"))
      (node (ref "U8") (pin "3") (pinfunction "A_3") (pintype "unspecified"))
    )
    (net (code "8") (name "BLDC1_PWM") (class "Default")
      (node (ref "CN1") (pin "6") (pinfunction "6_6") (pintype "unspecified"))
      (node (ref "U3") (pin "13") (pinfunction "B1_13") (pintype "unspecified"))
    )
    (net (code "9") (name "BLDC1_PWM_3V3") (class "Default")
      (node (ref "U1") (pin "62") (pinfunction "PD15_62") (pintype "unspecified"))
      (node (ref "U3") (pin "2") (pinfunction "A1_2") (pintype "unspecified"))
    )
    (net (code "10") (name "BLDC1_REV") (class "Default")
      (node (ref "CN1") (pin "5") (pinfunction "5_5") (pintype "unspecified"))
      (node (ref "U3") (pin "12") (pinfunction "B2_12") (pintype "unspecified"))
    )
    (net (code "11") (name "BLDC1_REV_3V3") (class "Default")
      (node (ref "U1") (pin "61") (pinfunction "PD14_61") (pintype "unspecified"))
      (node (ref "U3") (pin "3") (pinfunction "A2_3") (pintype "unspecified"))
    )
    (net (code "12") (name "BLDC2_24V") (class "Default")
      (node (ref "CN2") (pin "2") (pinfunction "2_2") (pintype "unspecified"))
    )
    (net (code "13") (name "BLDC2_BRA") (class "Default")
      (node (ref "CN2") (pin "4") (pinfunction "4_4") (pintype "unspecified"))
      (node (ref "U4") (pin "9") (pinfunction "NC_9") (pintype "unspecified"))
    )
    (net (code "14") (name "BLDC2_BRA_3V3") (class "Default")
      (node (ref "U1") (pin "33") (pinfunction "PC4_33") (pintype "unspecified"))
      (node (ref "U4") (pin "6") (pinfunction "NC_6") (pintype "unspecified"))
    )
    (net (code "15") (name "BLDC2_FG") (class "Default")
      (node (ref "CN2") (pin "3") (pinfunction "3_3") (pintype "unspecified"))
      (node (ref "U9") (pin "4") (pinfunction "B_4") (pintype "unspecified"))
    )
    (net (code "16") (name "BLDC2_FG_3V3") (class "Default")
      (node (ref "U1") (pin "31") (pinfunction "PA6_31") (pintype "unspecified"))
      (node (ref "U9") (pin "3") (pinfunction "A_3") (pintype "unspecified"))
    )
    (net (code "17") (name "BLDC2_PWM") (class "Default")
      (node (ref "CN2") (pin "6") (pinfunction "6_6") (pintype "unspecified"))
      (node (ref "U4") (pin "11") (pinfunction "B3_11") (pintype "unspecified"))
    )
    (net (code "18") (name "BLDC2_PWM_3V3") (class "Default")
      (node (ref "U1") (pin "36") (pinfunction "PB1_36") (pintype "unspecified"))
      (node (ref "U4") (pin "4") (pinfunction "A3_4") (pintype "unspecified"))
    )
    (net (code "19") (name "BLDC2_REV") (class "Default")
      (node (ref "CN2") (pin "5") (pinfunction "5_5") (pintype "unspecified"))
      (node (ref "U4") (pin "10") (pinfunction "B4_10") (pintype "unspecified"))
    )
    (net (code "20") (name "BLDC2_REV_3V3") (class "Default")
      (node (ref "U1") (pin "34") (pinfunction "PC5_34") (pintype "unspecified"))
      (node (ref "U4") (pin "5") (pinfunction "A4_5") (pintype "unspecified"))
    )
    (net (code "21") (name "BLDC3_24V") (class "Default")
      (node (ref "CN3") (pin "2") (pinfunction "2_2") (pintype "unspecified"))
    )
    (net (code "22") (name "BLDC3_BRA") (class "Default")
      (node (ref "CN3") (pin "3") (pinfunction "3_3") (pintype "unspecified"))
      (node (ref "U6") (pin "9") (pinfunction "NC_9") (pintype "unspecified"))
    )
    (net (code "23") (name "BLDC3_BRA_3V3") (class "Default")
      (node (ref "U1") (pin "25") (pinfunction "PA2_25") (pintype "unspecified"))
      (node (ref "U6") (pin "6") (pinfunction "NC_6") (pintype "unspecified"))
    )
    (net (code "24") (name "BLDC3_FG") (class "Default")
      (node (ref "CN3") (pin "6") (pinfunction "6_6") (pintype "unspecified"))
      (node (ref "U10") (pin "4") (pinfunction "B_4") (pintype "unspecified"))
    )
    (net (code "25") (name "BLDC3_FG_3V3") (class "Default")
      (node (ref "U1") (pin "24") (pinfunction "PA1_24") (pintype "unspecified"))
      (node (ref "U10") (pin "3") (pinfunction "A_3") (pintype "unspecified"))
    )
    (net (code "26") (name "BLDC3_PWM") (class "Default")
      (node (ref "CN3") (pin "4") (pinfunction "4_4") (pintype "unspecified"))
      (node (ref "U6") (pin "10") (pinfunction "B4_10") (pintype "unspecified"))
    )
    (net (code "27") (name "BLDC3_PWM_3V3") (class "Default")
      (node (ref "U1") (pin "26") (pinfunction "PA3_26") (pintype "unspecified"))
      (node (ref "U6") (pin "5") (pinfunction "A4_5") (pintype "unspecified"))
    )
    (net (code "28") (name "BLDC3_REV") (class "Default")
      (node (ref "CN3") (pin "5") (pinfunction "5_5") (pintype "unspecified"))
      (node (ref "U6") (pin "12") (pinfunction "B2_12") (pintype "unspecified"))
    )
    (net (code "29") (name "BLDC3_REV_3V3") (class "Default")
      (node (ref "U1") (pin "29") (pinfunction "PA4_29") (pintype "unspecified"))
      (node (ref "U6") (pin "3") (pinfunction "A2_3") (pintype "unspecified"))
    )
    (net (code "30") (name "BLDC4_24V") (class "Default")
      (node (ref "CN4") (pin "2") (pinfunction "2_2") (pintype "unspecified"))
    )
    (net (code "31") (name "BLDC4_BRA") (class "Default")
      (node (ref "CN4") (pin "4") (pinfunction "4_4") (pintype "unspecified"))
      (node (ref "U7") (pin "9") (pinfunction "NC_9") (pintype "unspecified"))
    )
    (net (code "32") (name "BLDC4_BRA_3V3") (class "Default")
      (node (ref "U1") (pin "42") (pinfunction "PE11_42") (pintype "unspecified"))
      (node (ref "U7") (pin "6") (pinfunction "NC_6") (pintype "unspecified"))
    )
    (net (code "33") (name "BLDC4_FG") (class "Default")
      (node (ref "CN4") (pin "3") (pinfunction "3_3") (pintype "unspecified"))
      (node (ref "U11") (pin "4") (pinfunction "B_4") (pintype "unspecified"))
    )
    (net (code "34") (name "BLDC4_FG_3V3") (class "Default")
      (node (ref "U1") (pin "40") (pinfunction "PE9_40") (pintype "unspecified"))
      (node (ref "U11") (pin "3") (pinfunction "A_3") (pintype "unspecified"))
    )
    (net (code "35") (name "BLDC4_PWM") (class "Default")
      (node (ref "CN4") (pin "6") (pinfunction "6_6") (pintype "unspecified"))
      (node (ref "U7") (pin "11") (pinfunction "B3_11") (pintype "unspecified"))
    )
    (net (code "36") (name "BLDC4_PWM_3V3") (class "Default")
      (node (ref "U1") (pin "45") (pinfunction "PE14_45") (pintype "unspecified"))
      (node (ref "U7") (pin "4") (pinfunction "A3_4") (pintype "unspecified"))
    )
    (net (code "37") (name "BLDC4_REV") (class "Default")
      (node (ref "CN4") (pin "5") (pinfunction "5_5") (pintype "unspecified"))
      (node (ref "U7") (pin "10") (pinfunction "B4_10") (pintype "unspecified"))
    )
    (net (code "38") (name "BLDC4_REV_3V3") (class "Default")
      (node (ref "U1") (pin "43") (pinfunction "PE12_43") (pintype "unspecified"))
      (node (ref "U7") (pin "5") (pinfunction "A4_5") (pintype "unspecified"))
    )
    (net (code "39") (name "BOOT0") (class "Default")
      (node (ref "H1") (pin "1") (pinfunction "1_1") (pintype "unspecified"))
      (node (ref "R4") (pin "2") (pinfunction "2_2") (pintype "input"))
      (node (ref "U1") (pin "94") (pinfunction "BOOT0_94") (pintype "unspecified"))
    )
    (net (code "40") (name "GND") (class "Default")
      (node (ref "C1") (pin "2") (pinfunction "2_2") (pintype "input"))
      (node (ref "C10") (pin "1") (pinfunction "1_1") (pintype "input"))
      (node (ref "C11") (pin "1") (pinfunction "1_1") (pintype "input"))
      (node (ref "C12") (pin "1") (pinfunction "1_1") (pintype "input"))
      (node (ref "C13") (pin "1") (pinfunction "1_1") (pintype "input"))
      (node (ref "C14") (pin "1") (pinfunction "1_1") (pintype "input"))
      (node (ref "C15") (pin "1") (pinfunction "1_1") (pintype "input"))
      (node (ref "C16") (pin "1") (pinfunction "1_1") (pintype "input"))
      (node (ref "C17") (pin "1") (pinfunction "1_1") (pintype "input"))
      (node (ref "C18") (pin "1") (pinfunction "1_1") (pintype "input"))
      (node (ref "C19") (pin "2") (pinfunction "2_2") (pintype "input"))
      (node (ref "C2") (pin "1") (pinfunction "1_1") (pintype "input"))
      (node (ref "C20") (pin "2") (pinfunction "2_2") (pintype "input"))
      (node (ref "C21") (pin "2") (pinfunction "2_2") (pintype "input"))
      (node (ref "C22") (pin "2") (pinfunction "2_2") (pintype "input"))
      (node (ref "C24") (pin "2") (pinfunction "2_2") (pintype "input"))
      (node (ref "C25") (pin "2") (pinfunction "2_2") (pintype "input"))
      (node (ref "C26") (pin "1") (pinfunction "1_1") (pintype "unspecified"))
      (node (ref "C27") (pin "2") (pinfunction "2_2") (pintype "input"))
      (node (ref "C28") (pin "2") (pinfunction "2_2") (pintype "input"))
      (node (ref "C29") (pin "2") (pinfunction "2_2") (pintype "input"))
      (node (ref "C3") (pin "1") (pinfunction "1_1") (pintype "input"))
      (node (ref "C30") (pin "2") (pinfunction "2_2") (pintype "input"))
      (node (ref "C32") (pin "2") (pinfunction "2_2") (pintype "input"))
      (node (ref "C33") (pin "2") (pinfunction "2_2") (pintype "input"))
      (node (ref "C34") (pin "1") (pinfunction "1_1") (pintype "unspecified"))
      (node (ref "C35") (pin "2") (pinfunction "2_2") (pintype "input"))
      (node (ref "C36") (pin "2") (pinfunction "2_2") (pintype "input"))
      (node (ref "C37") (pin "2") (pinfunction "2_2") (pintype "input"))
      (node (ref "C38") (pin "2") (pinfunction "2_2") (pintype "input"))
      (node (ref "C39") (pin "2") (pinfunction "2_2") (pintype "input"))
      (node (ref "C4") (pin "1") (pinfunction "1_1") (pintype "input"))
      (node (ref "C40") (pin "2") (pinfunction "2_2") (pintype "input"))
      (node (ref "C41") (pin "2") (pinfunction "2_2") (pintype "input"))
      (node (ref "C42") (pin "2") (pinfunction "2_2") (pintype "input"))
      (node (ref "C43") (pin "1") (pinfunction "1_1") (pintype "input"))
      (node (ref "C5") (pin "1") (pinfunction "1_1") (pintype "input"))
      (node (ref "C6") (pin "1") (pinfunction "1_1") (pintype "input"))
      (node (ref "C7") (pin "1") (pinfunction "1_1") (pintype "input"))
      (node (ref "C8") (pin "1") (pinfunction "1_1") (pintype "input"))
      (node (ref "C9") (pin "1") (pinfunction "1_1") (pintype "input"))
      (node (ref "CN1") (pin "1") (pinfunction "1_1") (pintype "unspecified"))
      (node (ref "CN2") (pin "1") (pinfunction "1_1") (pintype "unspecified"))
      (node (ref "CN3") (pin "1") (pinfunction "1_1") (pintype "unspecified"))
      (node (ref "CN4") (pin "1") (pinfunction "1_1") (pintype "unspecified"))
      (node (ref "CN6") (pin "4") (pinfunction "4_4") (pintype "unspecified"))
      (node (ref "D1") (pin "1") (pinfunction "A_1") (pintype "unspecified"))
      (node (ref "D2") (pin "1") (pinfunction "A_1") (pintype "unspecified"))
      (node (ref "H1") (pin "3") (pinfunction "3_3") (pintype "unspecified"))
      (node (ref "H2") (pin "3") (pinfunction "3_3") (pintype "unspecified"))
      (node (ref "LED1") (pin "2") (pinfunction "-_2") (pintype "unspecified"))
      (node (ref "LED2") (pin "2") (pinfunction "-_2") (pintype "unspecified"))
      (node (ref "P1") (pin "1") (pinfunction "1_1") (pintype "unspecified"))
      (node (ref "Q1") (pin "2") (pinfunction "E_2") (pintype "input"))
      (node (ref "R11") (pin "1") (pinfunction "1_1") (pintype "input"))
      (node (ref "R4") (pin "1") (pinfunction "1_1") (pintype "input"))
      (node (ref "R5") (pin "1") (pinfunction "1_1") (pintype "input"))
      (node (ref "R8") (pin "1") (pinfunction "1_1") (pintype "input"))
      (node (ref "SW1") (pin "1") (pinfunction "1_1") (pintype "unspecified"))
      (node (ref "U1") (pin "10") (pinfunction "VSS_10") (pintype "unspecified"))
      (node (ref "U1") (pin "20") (pinfunction "VSSA_20") (pintype "unspecified"))
      (node (ref "U1") (pin "27") (pinfunction "VSS_27") (pintype "unspecified"))
      (node (ref "U1") (pin "74") (pinfunction "VSS_74") (pintype "unspecified"))
      (node (ref "U1") (pin "99") (pinfunction "VSS_99") (pintype "unspecified"))
      (node (ref "U10") (pin "2") (pinfunction "GND_2") (pintype "unspecified"))
      (node (ref "U10") (pin "5") (pinfunction "DIR_5") (pintype "unspecified"))
      (node (ref "U11") (pin "2") (pinfunction "GND_2") (pintype "unspecified"))
      (node (ref "U11") (pin "5") (pinfunction "DIR_5") (pintype "unspecified"))
      (node (ref "U12") (pin "4") (pinfunction "GND_4") (pintype "unspecified"))
      (node (ref "U13") (pin "12") (pinfunction "12_12") (pintype "unspecified"))
      (node (ref "U2") (pin "6") (pinfunction "GND_6") (pintype "unspecified"))
      (node (ref "U2") (pin "9") (pinfunction "PowerPAD_9") (pintype "unspecified"))
      (node (ref "U3") (pin "7") (pinfunction "GND_7") (pintype "unspecified"))
      (node (ref "U4") (pin "7") (pinfunction "GND_7") (pintype "unspecified"))
      (node (ref "U5") (pin "6") (pinfunction "GND_6") (pintype "unspecified"))
      (node (ref "U5") (pin "9") (pinfunction "PowerPAD_9") (pintype "unspecified"))
      (node (ref "U6") (pin "7") (pinfunction "GND_7") (pintype "unspecified"))
      (node (ref "U7") (pin "7") (pinfunction "GND_7") (pintype "unspecified"))
      (node (ref "U8") (pin "2") (pinfunction "GND_2") (pintype "unspecified"))
      (node (ref "U8") (pin "5") (pinfunction "DIR_5") (pintype "unspecified"))
      (node (ref "U9") (pin "2") (pinfunction "GND_2") (pintype "unspecified"))
      (node (ref "U9") (pin "5") (pinfunction "DIR_5") (pintype "unspecified"))
      (node (ref "X3") (pin "2") (pinfunction "GND_2") (pintype "unspecified"))
      (node (ref "X3") (pin "4") (pinfunction "GND_4") (pintype "unspecified"))
    )
    (net (code "41") (name "I2C1_SCL") (class "Default")
      (node (ref "U1") (pin "92") (pinfunction "PB6_92") (pintype "unspecified"))
      (node (ref "U27") (pin "2") (pinfunction "2_2") (pintype "unspecified"))
    )
    (net (code "42") (name "I2C1_SDA") (class "Default")
      (node (ref "U1") (pin "93") (pinfunction "PB7_93") (pintype "unspecified"))
      (node (ref "U27") (pin "1") (pinfunction "1_1") (pintype "unspecified"))
    )
    (net (code "43") (name "MC7RE_SBUS") (class "Default")
      (node (ref "H2") (pin "1") (pinfunction "1_1") (pintype "unspecified"))
      (node (ref "R13") (pin "2") (pinfunction "2_2") (pintype "input"))
    )
    (net (code "44") (name "Net-(D1-K)") (class "Default")
      (node (ref "C23") (pin "1") (pinfunction "1_1") (pintype "input"))
      (node (ref "D1") (pin "2") (pinfunction "K_2") (pintype "unspecified"))
      (node (ref "L1") (pin "2") (pinfunction "2_2") (pintype "unspecified"))
      (node (ref "U2") (pin "8") (pinfunction "PH_8") (pintype "unspecified"))
    )
    (net (code "45") (name "Net-(D2-K)") (class "Default")
      (node (ref "C31") (pin "1") (pinfunction "1_1") (pintype "input"))
      (node (ref "D2") (pin "2") (pinfunction "K_2") (pintype "unspecified"))
      (node (ref "L2") (pin "2") (pinfunction "2_2") (pintype "unspecified"))
      (node (ref "U5") (pin "8") (pinfunction "PH_8") (pintype "unspecified"))
    )
    (net (code "46") (name "Net-(LED1-+)") (class "Default")
      (node (ref "LED1") (pin "1") (pinfunction "+_1") (pintype "unspecified"))
      (node (ref "R2") (pin "1") (pinfunction "1_1") (pintype "input"))
    )
    (net (code "47") (name "Net-(LED2-+)") (class "Default")
      (node (ref "LED2") (pin "1") (pinfunction "+_1") (pintype "unspecified"))
      (node (ref "R14") (pin "1") (pinfunction "1_1") (pintype "input"))
    )
    (net (code "48") (name "Net-(P1-Pad2)") (class "Default")
      (node (ref "P1") (pin "2") (pinfunction "2_2") (pintype "unspecified"))
      (node (ref "U24") (pin "2") (pinfunction "2_2") (pintype "unspecified"))
    )
    (net (code "49") (name "Net-(Q1-B)") (class "Default")
      (node (ref "Q1") (pin "1") (pinfunction "B_1") (pintype "input"))
      (node (ref "R13") (pin "1") (pinfunction "1_1") (pintype "input"))
    )
    (net (code "50") (name "Net-(U1-NRST)") (class "Default")
      (node (ref "C8") (pin "2") (pinfunction "2_2") (pintype "input"))
      (node (ref "SW1") (pin "2") (pinfunction "2_2") (pintype "unspecified"))
      (node (ref "U1") (pin "14") (pinfunction "NRST_14") (pintype "unspecified"))
    )
    (net (code "51") (name "Net-(U1-PB2)") (class "Default")
      (node (ref "R5") (pin "2") (pinfunction "2_2") (pintype "input"))
      (node (ref "U1") (pin "37") (pinfunction "PB2_37") (pintype "unspecified"))
    )
    (net (code "52") (name "Net-(U1-PC14)") (class "Default")
      (node (ref "C7") (pin "2") (pinfunction "2_2") (pintype "input"))
      (node (ref "U1") (pin "8") (pinfunction "PC14_8") (pintype "unspecified"))
      (node (ref "X2") (pin "2") (pinfunction "2_2") (pintype "unspecified"))
    )
    (net (code "53") (name "Net-(U1-PC15)") (class "Default")
      (node (ref "C9") (pin "2") (pinfunction "2_2") (pintype "input"))
      (node (ref "U1") (pin "9") (pinfunction "PC15_9") (pintype "unspecified"))
      (node (ref "X2") (pin "1") (pinfunction "1_1") (pintype "unspecified"))
    )
    (net (code "54") (name "Net-(U1-PH0)") (class "Default")
      (node (ref "C2") (pin "2") (pinfunction "2_2") (pintype "input"))
      (node (ref "U1") (pin "12") (pinfunction "PH0_12") (pintype "unspecified"))
      (node (ref "X3") (pin "3") (pinfunction "OSC2_3") (pintype "unspecified"))
    )
    (net (code "55") (name "Net-(U1-PH1)") (class "Default")
      (node (ref "C3") (pin "2") (pinfunction "2_2") (pintype "input"))
      (node (ref "U1") (pin "13") (pinfunction "PH1_13") (pintype "unspecified"))
      (node (ref "X3") (pin "1") (pinfunction "OSC1_1") (pintype "unspecified"))
    )
    (net (code "56") (name "Net-(U1-VCAP_1)") (class "Default")
      (node (ref "C5") (pin "2") (pinfunction "2_2") (pintype "input"))
      (node (ref "U1") (pin "49") (pinfunction "VCAP_1_49") (pintype "unspecified"))
    )
    (net (code "57") (name "Net-(U1-VCAP_2)") (class "Default")
      (node (ref "C6") (pin "2") (pinfunction "2_2") (pintype "input"))
      (node (ref "U1") (pin "73") (pinfunction "VCAP_2_73") (pintype "unspecified"))
    )
    (net (code "58") (name "Net-(U1-VREF+)") (class "Default")
      (node (ref "R3") (pin "1") (pinfunction "1_1") (pintype "input"))
      (node (ref "U1") (pin "21") (pinfunction "VREF+_21") (pintype "unspecified"))
    )
    (net (code "59") (name "Net-(U2-BOOT)") (class "Default")
      (node (ref "C23") (pin "2") (pinfunction "2_2") (pintype "input"))
      (node (ref "U2") (pin "1") (pinfunction "BOOT_1") (pintype "unspecified"))
    )
    (net (code "60") (name "Net-(U5-BOOT)") (class "Default")
      (node (ref "C31") (pin "2") (pinfunction "2_2") (pintype "input"))
      (node (ref "U5") (pin "1") (pinfunction "BOOT_1") (pintype "unspecified"))
    )
    (net (code "61") (name "PUMP_IN1") (class "Default")
      (node (ref "CN6") (pin "2") (pinfunction "2_2") (pintype "unspecified"))
      (node (ref "U1") (pin "96") (pinfunction "PB9_96") (pintype "unspecified"))
    )
    (net (code "62") (name "PUMP_IN2") (class "Default")
      (node (ref "CN6") (pin "1") (pinfunction "1_1") (pintype "unspecified"))
      (node (ref "U1") (pin "95") (pinfunction "PB8_95") (pintype "unspecified"))
    )
    (net (code "63") (name "PUMP_VREF") (class "Default")
      (node (ref "CN6") (pin "3") (pinfunction "3_3") (pintype "unspecified"))
      (node (ref "U1") (pin "97") (pinfunction "PE0_97") (pintype "unspecified"))
    )
    (net (code "64") (name "REMOTE_DATA") (class "Default")
      (node (ref "Q1") (pin "3") (pinfunction "C_3") (pintype "input"))
      (node (ref "R12") (pin "1") (pinfunction "1_1") (pintype "input"))
      (node (ref "U1") (pin "87") (pinfunction "PD6_87") (pintype "unspecified"))
    )
    (net (code "65") (name "SPI3_CS") (class "Default")
      (node (ref "U1") (pin "77") (pinfunction "PA15_77") (pintype "unspecified"))
      (node (ref "U12") (pin "1") (pinfunction "CS#_1") (pintype "unspecified"))
    )
    (net (code "66") (name "SPI3_MISO") (class "Default")
      (node (ref "U1") (pin "79") (pinfunction "PC11_79") (pintype "unspecified"))
      (node (ref "U12") (pin "2") (pinfunction "DO/IO1_2") (pintype "unspecified"))
    )
    (net (code "67") (name "SPI3_MOSI") (class "Default")
      (node (ref "U1") (pin "91") (pinfunction "PB5_91") (pintype "unspecified"))
      (node (ref "U12") (pin "5") (pinfunction "DI/IO0_5") (pintype "unspecified"))
    )
    (net (code "68") (name "SPI3_SCK") (class "Default")
      (node (ref "U1") (pin "78") (pinfunction "PC10_78") (pintype "unspecified"))
      (node (ref "U12") (pin "6") (pinfunction "CLK_6") (pintype "unspecified"))
    )
    (net (code "69") (name "STEPPER_DECAY") (class "Default")
      (node (ref "U1") (pin "57") (pinfunction "PD10_57") (pintype "unspecified"))
      (node (ref "U13") (pin "8") (pinfunction "8_8") (pintype "unspecified"))
    )
    (net (code "70") (name "STEPPER_DIR") (class "Default")
      (node (ref "U1") (pin "56") (pinfunction "PD9_56") (pintype "unspecified"))
      (node (ref "U13") (pin "7") (pinfunction "7_7") (pintype "unspecified"))
    )
    (net (code "71") (name "STEPPER_MODE0") (class "Default")
      (node (ref "U1") (pin "53") (pinfunction "PB14_53") (pintype "unspecified"))
      (node (ref "U13") (pin "4") (pinfunction "4_4") (pintype "unspecified"))
    )
    (net (code "72") (name "STEPPER_MODE1") (class "Default")
      (node (ref "U1") (pin "52") (pinfunction "PB13_52") (pintype "unspecified"))
      (node (ref "U13") (pin "3") (pinfunction "3_3") (pintype "unspecified"))
    )
    (net (code "73") (name "STEPPER_MODE2") (class "Default")
      (node (ref "U1") (pin "51") (pinfunction "PB12_51") (pintype "unspecified"))
      (node (ref "U13") (pin "2") (pinfunction "2_2") (pintype "unspecified"))
    )
    (net (code "74") (name "STEPPER_NENBL") (class "Default")
      (node (ref "U1") (pin "55") (pinfunction "PD8_55") (pintype "unspecified"))
      (node (ref "U13") (pin "6") (pinfunction "6_6") (pintype "unspecified"))
    )
    (net (code "75") (name "STEPPER_NFLT") (class "Default")
      (node (ref "U1") (pin "63") (pinfunction "PC6_63") (pintype "unspecified"))
      (node (ref "U13") (pin "9") (pinfunction "9_9") (pintype "unspecified"))
    )
    (net (code "76") (name "STEPPER_NHOME") (class "Default")
      (node (ref "U1") (pin "46") (pinfunction "PE15_46") (pintype "unspecified"))
      (node (ref "U13") (pin "1") (pinfunction "1_1") (pintype "unspecified"))
    )
    (net (code "77") (name "STEPPER_NRST") (class "Default")
      (node (ref "U1") (pin "65") (pinfunction "PC8_65") (pintype "unspecified"))
      (node (ref "U13") (pin "11") (pinfunction "11_11") (pintype "unspecified"))
    )
    (net (code "78") (name "STEPPER_NSLP") (class "Default")
      (node (ref "U1") (pin "64") (pinfunction "PC7_64") (pintype "unspecified"))
      (node (ref "U13") (pin "10") (pinfunction "10_10") (pintype "unspecified"))
    )
    (net (code "79") (name "STEPPER_STEP") (class "Default")
      (node (ref "U1") (pin "54") (pinfunction "PB15_54") (pintype "unspecified"))
      (node (ref "U13") (pin "5") (pinfunction "5_5") (pintype "unspecified"))
    )
    (net (code "80") (name "SWCLK") (class "Default")
      (node (ref "H1") (pin "5") (pinfunction "5_5") (pintype "unspecified"))
      (node (ref "U1") (pin "76") (pinfunction "PA14_76") (pintype "unspecified"))
    )
    (net (code "81") (name "SWDIO") (class "Default")
      (node (ref "H1") (pin "4") (pinfunction "4_4") (pintype "unspecified"))
      (node (ref "U1") (pin "72") (pinfunction "PA13_72") (pintype "unspecified"))
    )
    (net (code "82") (name "UART5_RX") (class "Default")
      (node (ref "U1") (pin "83") (pinfunction "PD2_83") (pintype "unspecified"))
      (node (ref "U28") (pin "2") (pinfunction "2_2") (pintype "unspecified"))
    )
    (net (code "83") (name "UART5_TX") (class "Default")
      (node (ref "U1") (pin "80") (pinfunction "PC12_80") (pintype "unspecified"))
      (node (ref "U28") (pin "1") (pinfunction "1_1") (pintype "unspecified"))
    )
    (net (code "84") (name "USART1_RX") (class "Default")
      (node (ref "U1") (pin "69") (pinfunction "PA10_69") (pintype "unspecified"))
      (node (ref "U26") (pin "2") (pinfunction "2_2") (pintype "unspecified"))
    )
    (net (code "85") (name "USART1_TX") (class "Default")
      (node (ref "U1") (pin "68") (pinfunction "PA9_68") (pintype "unspecified"))
      (node (ref "U26") (pin "1") (pinfunction "1_1") (pintype "unspecified"))
    )
    (net (code "86") (name "VDDA") (class "Default")
      (node (ref "C1") (pin "1") (pinfunction "1_1") (pintype "input"))
      (node (ref "C18") (pin "2") (pinfunction "2_2") (pintype "input"))
      (node (ref "R1") (pin "2") (pinfunction "2_2") (pintype "input"))
      (node (ref "R3") (pin "2") (pinfunction "2_2") (pintype "input"))
      (node (ref "U1") (pin "22") (pinfunction "VDDA_22") (pintype "unspecified"))
    )
    (net (code "87") (name "VIN_24V") (class "Default")
      (node (ref "C25") (pin "1") (pinfunction "1_1") (pintype "input"))
      (node (ref "C26") (pin "2") (pinfunction "2_2") (pintype "unspecified"))
      (node (ref "C33") (pin "1") (pinfunction "1_1") (pintype "input"))
      (node (ref "C34") (pin "2") (pinfunction "2_2") (pintype "unspecified"))
      (node (ref "U2") (pin "7") (pinfunction "VIN_7") (pintype "unspecified"))
      (node (ref "U24") (pin "3") (pinfunction "3_3") (pintype "unspecified"))
      (node (ref "U5") (pin "7") (pinfunction "VIN_7") (pintype "unspecified"))
    )
    (net (code "88") (name "VSEN_3V3") (class "Default")
      (node (ref "R6") (pin "1") (pinfunction "1_1") (pintype "input"))
      (node (ref "R8") (pin "2") (pinfunction "2_2") (pintype "input"))
      (node (ref "U2") (pin "4") (pinfunction "VSENSE_4") (pintype "unspecified"))
    )
    (net (code "89") (name "VSEN_5V") (class "Default")
      (node (ref "R11") (pin "2") (pinfunction "2_2") (pintype "input"))
      (node (ref "R9") (pin "1") (pinfunction "1_1") (pintype "input"))
      (node (ref "U5") (pin "4") (pinfunction "VSENSE_4") (pintype "unspecified"))
    )
    (net (code "90") (name "unconnected-(U1-PA0-Pad23)") (class "Default")
      (node (ref "U1") (pin "23") (pinfunction "PA0_23") (pintype "unspecified"))
    )
    (net (code "91") (name "unconnected-(U1-PA5-Pad30)") (class "Default")
      (node (ref "U1") (pin "30") (pinfunction "PA5_30") (pintype "unspecified"))
    )
    (net (code "92") (name "unconnected-(U1-PA7-Pad32)") (class "Default")
      (node (ref "U1") (pin "32") (pinfunction "PA7_32") (pintype "unspecified"))
    )
    (net (code "93") (name "unconnected-(U1-PA8-Pad67)") (class "Default")
      (node (ref "U1") (pin "67") (pinfunction "PA8_67") (pintype "unspecified"))
    )
    (net (code "94") (name "unconnected-(U1-PA11-Pad70)") (class "Default")
      (node (ref "U1") (pin "70") (pinfunction "PA11_70") (pintype "unspecified"))
    )
    (net (code "95") (name "unconnected-(U1-PA12-Pad71)") (class "Default")
      (node (ref "U1") (pin "71") (pinfunction "PA12_71") (pintype "unspecified"))
    )
    (net (code "96") (name "unconnected-(U1-PB0-Pad35)") (class "Default")
      (node (ref "U1") (pin "35") (pinfunction "PB0_35") (pintype "unspecified"))
    )
    (net (code "97") (name "unconnected-(U1-PB3-Pad89)") (class "Default")
      (node (ref "U1") (pin "89") (pinfunction "PB3_89") (pintype "unspecified"))
    )
    (net (code "98") (name "unconnected-(U1-PB4-Pad90)") (class "Default")
      (node (ref "U1") (pin "90") (pinfunction "PB4_90") (pintype "unspecified"))
    )
    (net (code "99") (name "unconnected-(U1-PB10-Pad47)") (class "Default")
      (node (ref "U1") (pin "47") (pinfunction "PB10_47") (pintype "unspecified"))
    )
    (net (code "100") (name "unconnected-(U1-PB11-Pad48)") (class "Default")
      (node (ref "U1") (pin "48") (pinfunction "PB11_48") (pintype "unspecified"))
    )
    (net (code "101") (name "unconnected-(U1-PC0-Pad15)") (class "Default")
      (node (ref "U1") (pin "15") (pinfunction "PC0_15") (pintype "unspecified"))
    )
    (net (code "102") (name "unconnected-(U1-PC1-Pad16)") (class "Default")
      (node (ref "U1") (pin "16") (pinfunction "PC1_16") (pintype "unspecified"))
    )
    (net (code "103") (name "unconnected-(U1-PC2-Pad17)") (class "Default")
      (node (ref "U1") (pin "17") (pinfunction "PC2_17") (pintype "unspecified"))
    )
    (net (code "104") (name "unconnected-(U1-PC3-Pad18)") (class "Default")
      (node (ref "U1") (pin "18") (pinfunction "PC3_18") (pintype "unspecified"))
    )
    (net (code "105") (name "unconnected-(U1-PC9-Pad66)") (class "Default")
      (node (ref "U1") (pin "66") (pinfunction "PC9_66") (pintype "unspecified"))
    )
    (net (code "106") (name "unconnected-(U1-PC13-Pad7)") (class "Default")
      (node (ref "U1") (pin "7") (pinfunction "PC13_7") (pintype "unspecified"))
    )
    (net (code "107") (name "unconnected-(U1-PD0-Pad81)") (class "Default")
      (node (ref "U1") (pin "81") (pinfunction "PD0_81") (pintype "unspecified"))
    )
    (net (code "108") (name "unconnected-(U1-PD1-Pad82)") (class "Default")
      (node (ref "U1") (pin "82") (pinfunction "PD1_82") (pintype "unspecified"))
    )
    (net (code "109") (name "unconnected-(U1-PD3-Pad84)") (class "Default")
      (node (ref "U1") (pin "84") (pinfunction "PD3_84") (pintype "unspecified"))
    )
    (net (code "110") (name "unconnected-(U1-PD4-Pad85)") (class "Default")
      (node (ref "U1") (pin "85") (pinfunction "PD4_85") (pintype "unspecified"))
    )
    (net (code "111") (name "unconnected-(U1-PD5-Pad86)") (class "Default")
      (node (ref "U1") (pin "86") (pinfunction "PD5_86") (pintype "unspecified"))
    )
    (net (code "112") (name "unconnected-(U1-PD7-Pad88)") (class "Default")
      (node (ref "U1") (pin "88") (pinfunction "PD7_88") (pintype "unspecified"))
    )
    (net (code "113") (name "unconnected-(U1-PD11-Pad58)") (class "Default")
      (node (ref "U1") (pin "58") (pinfunction "PD11_58") (pintype "unspecified"))
    )
    (net (code "114") (name "unconnected-(U1-PE1-Pad98)") (class "Default")
      (node (ref "U1") (pin "98") (pinfunction "PE1_98") (pintype "unspecified"))
    )
    (net (code "115") (name "unconnected-(U1-PE2-Pad1)") (class "Default")
      (node (ref "U1") (pin "1") (pinfunction "PE2_1") (pintype "unspecified"))
    )
    (net (code "116") (name "unconnected-(U1-PE3-Pad2)") (class "Default")
      (node (ref "U1") (pin "2") (pinfunction "PE3_2") (pintype "unspecified"))
    )
    (net (code "117") (name "unconnected-(U1-PE4-Pad3)") (class "Default")
      (node (ref "U1") (pin "3") (pinfunction "PE4_3") (pintype "unspecified"))
    )
    (net (code "118") (name "unconnected-(U1-PE5-Pad4)") (class "Default")
      (node (ref "U1") (pin "4") (pinfunction "PE5_4") (pintype "unspecified"))
    )
    (net (code "119") (name "unconnected-(U1-PE6-Pad5)") (class "Default")
      (node (ref "U1") (pin "5") (pinfunction "PE6_5") (pintype "unspecified"))
    )
    (net (code "120") (name "unconnected-(U1-PE7-Pad38)") (class "Default")
      (node (ref "U1") (pin "38") (pinfunction "PE7_38") (pintype "unspecified"))
    )
    (net (code "121") (name "unconnected-(U1-PE8-Pad39)") (class "Default")
      (node (ref "U1") (pin "39") (pinfunction "PE8_39") (pintype "unspecified"))
    )
    (net (code "122") (name "unconnected-(U1-PE10-Pad41)") (class "Default")
      (node (ref "U1") (pin "41") (pinfunction "PE10_41") (pintype "unspecified"))
    )
    (net (code "123") (name "unconnected-(U1-PE13-Pad44)") (class "Default")
      (node (ref "U1") (pin "44") (pinfunction "PE13_44") (pintype "unspecified"))
    )
    (net (code "124") (name "unconnected-(U2-ENA-Pad5)") (class "Default")
      (node (ref "U2") (pin "5") (pinfunction "ENA_5") (pintype "unspecified+no_connect"))
    )
    (net (code "125") (name "unconnected-(U2-NC-Pad2)") (class "Default")
      (node (ref "U2") (pin "2") (pinfunction "NC_2") (pintype "unspecified+no_connect"))
    )
    (net (code "126") (name "unconnected-(U2-NC-Pad3)") (class "Default")
      (node (ref "U2") (pin "3") (pinfunction "NC_3") (pintype "unspecified+no_connect"))
    )
    (net (code "127") (name "unconnected-(U3-A3-Pad4)") (class "Default")
      (node (ref "U3") (pin "4") (pinfunction "A3_4") (pintype "unspecified"))
    )
    (net (code "128") (name "unconnected-(U3-B3-Pad11)") (class "Default")
      (node (ref "U3") (pin "11") (pinfunction "B3_11") (pintype "unspecified"))
    )
    (net (code "129") (name "unconnected-(U3-NC-Pad6)") (class "Default")
      (node (ref "U3") (pin "6") (pinfunction "NC_6") (pintype "unspecified"))
    )
    (net (code "130") (name "unconnected-(U3-NC-Pad9)") (class "Default")
      (node (ref "U3") (pin "9") (pinfunction "NC_9") (pintype "unspecified"))
    )
    (net (code "131") (name "unconnected-(U4-A1-Pad2)") (class "Default")
      (node (ref "U4") (pin "2") (pinfunction "A1_2") (pintype "unspecified"))
    )
    (net (code "132") (name "unconnected-(U4-A2-Pad3)") (class "Default")
      (node (ref "U4") (pin "3") (pinfunction "A2_3") (pintype "unspecified"))
    )
    (net (code "133") (name "unconnected-(U4-B1-Pad13)") (class "Default")
      (node (ref "U4") (pin "13") (pinfunction "B1_13") (pintype "unspecified"))
    )
    (net (code "134") (name "unconnected-(U4-B2-Pad12)") (class "Default")
      (node (ref "U4") (pin "12") (pinfunction "B2_12") (pintype "unspecified"))
    )
    (net (code "135") (name "unconnected-(U5-ENA-Pad5)") (class "Default")
      (node (ref "U5") (pin "5") (pinfunction "ENA_5") (pintype "unspecified+no_connect"))
    )
    (net (code "136") (name "unconnected-(U5-NC-Pad2)") (class "Default")
      (node (ref "U5") (pin "2") (pinfunction "NC_2") (pintype "unspecified+no_connect"))
    )
    (net (code "137") (name "unconnected-(U5-NC-Pad3)") (class "Default")
      (node (ref "U5") (pin "3") (pinfunction "NC_3") (pintype "unspecified+no_connect"))
    )
    (net (code "138") (name "unconnected-(U6-A1-Pad2)") (class "Default")
      (node (ref "U6") (pin "2") (pinfunction "A1_2") (pintype "unspecified"))
    )
    (net (code "139") (name "unconnected-(U6-A3-Pad4)") (class "Default")
      (node (ref "U6") (pin "4") (pinfunction "A3_4") (pintype "unspecified"))
    )
    (net (code "140") (name "unconnected-(U6-B1-Pad13)") (class "Default")
      (node (ref "U6") (pin "13") (pinfunction "B1_13") (pintype "unspecified"))
    )
    (net (code "141") (name "unconnected-(U6-B3-Pad11)") (class "Default")
      (node (ref "U6") (pin "11") (pinfunction "B3_11") (pintype "unspecified"))
    )
    (net (code "142") (name "unconnected-(U7-A1-Pad2)") (class "Default")
      (node (ref "U7") (pin "2") (pinfunction "A1_2") (pintype "unspecified"))
    )
    (net (code "143") (name "unconnected-(U7-A2-Pad3)") (class "Default")
      (node (ref "U7") (pin "3") (pinfunction "A2_3") (pintype "unspecified"))
    )
    (net (code "144") (name "unconnected-(U7-B1-Pad13)") (class "Default")
      (node (ref "U7") (pin "13") (pinfunction "B1_13") (pintype "unspecified"))
    )
    (net (code "145") (name "unconnected-(U7-B2-Pad12)") (class "Default")
      (node (ref "U7") (pin "12") (pinfunction "B2_12") (pintype "unspecified"))
    )
    (net (code "146") (name "unconnected-(U24-Pad1)") (class "Default")
      (node (ref "U24") (pin "1") (pinfunction "1_1") (pintype "unspecified+no_connect"))
    )
  )
)
